# microsd.net
KiCad netlist of a schematic drawn in Altium Designer
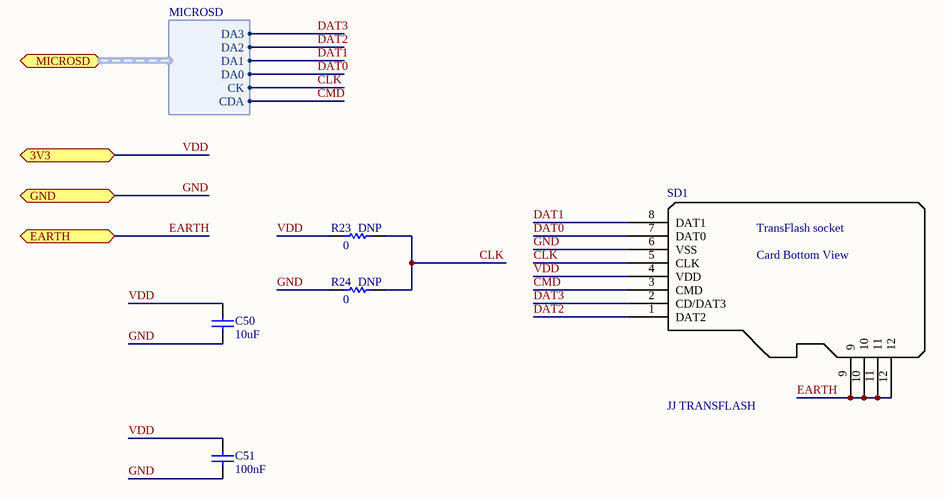
[diagram p0: microsd.SchDoc]

(export (version "E")
  (design (tool "Eeschema 10.0.6"))
  (components
    (comp (ref "C50")
      (value "10uF")
      (footprint "0805")
      (fields (field (name "TOLERANCE") "5%") (field (name "VOLTAGE") "25V") (field (name "Comment") "CAP"))
      (libsource (lib "gasctrl") (part "CAP"))
    )
    (comp (ref "C51")
      (value "100nF")
      (footprint "0805")
      (fields (field (name "TOLERANCE") "5%") (field (name "VOLTAGE") "25V") (field (name "Comment") "CAP"))
      (libsource (lib "gasctrl") (part "CAP"))
    )
    (comp (ref "R23")
      (value "0")
      (footprint "gasctrl:0805")
      (description "RES 0805 0.0 OHM .33W")
      (fields
        (field (name "MANUFACTURER") "Vishay Dale")
        (field (name "POWER") ".33W")
        (field (name "DO NOT PLACE") "DNP")
      )
      (libsource (lib "gasctrl") (part "RES 0805 0.0 Ohm .33W"))
    )
    (comp (ref "R24")
      (value "0")
      (footprint "gasctrl:0805")
      (description "RES 0805 0.0 OHM .33W")
      (fields
        (field (name "MANUFACTURER") "Vishay Dale")
        (field (name "POWER") ".33W")
        (field (name "DO NOT PLACE") "DNP")
      )
      (libsource (lib "gasctrl") (part "RES 0805 0.0 Ohm .33W"))
    )
    (comp (ref "SD1")
      (value "JJ TRANSFLASH")
      (footprint "microSD Socket")
      (description "Transflash Socket")
      (libsource (lib "Schematics") (part "JJ TRANSFLASH"))
    )
  )
  (nets
    (net (code "2") (name "/CLK") (class "Default")
      (node (ref "R23") (pin "2") (pinfunction "2_2") (pintype "passive"))
      (node (ref "R24") (pin "2") (pinfunction "2_2") (pintype "passive"))
      (node (ref "SD1") (pin "5") (pinfunction "CLK_5") (pintype "passive"))
    )
    (net (code "3") (name "/CMD") (class "Default")
      (node (ref "SD1") (pin "3") (pinfunction "CMD_3") (pintype "passive"))
    )
    (net (code "4") (name "/DAT0") (class "Default")
      (node (ref "SD1") (pin "7") (pinfunction "DAT0_7") (pintype "passive"))
    )
    (net (code "5") (name "/DAT1") (class "Default")
      (node (ref "SD1") (pin "8") (pinfunction "DAT1_8") (pintype "passive"))
    )
    (net (code "6") (name "/DAT2") (class "Default")
      (node (ref "SD1") (pin "1") (pinfunction "DAT2_1") (pintype "passive"))
    )
    (net (code "7") (name "/DAT3") (class "Default")
      (node (ref "SD1") (pin "2") (pinfunction "CD/DAT3_2") (pintype "passive"))
    )
    (net (code "8") (name "/EARTH") (class "Default")
      (node (ref "SD1") (pin "10") (pinfunction "10_10") (pintype "passive"))
      (node (ref "SD1") (pin "11") (pinfunction "11_11") (pintype "passive"))
      (node (ref "SD1") (pin "12") (pinfunction "12_12") (pintype "passive"))
      (node (ref "SD1") (pin "9") (pinfunction "9_9") (pintype "passive"))
    )
    (net (code "9") (name "/GND") (class "Default")
      (node (ref "C50") (pin "1") (pinfunction "1_1") (pintype "passive"))
      (node (ref "C51") (pin "1") (pinfunction "1_1") (pintype "passive"))
      (node (ref "R24") (pin "1") (pinfunction "1_1") (pintype "passive"))
      (node (ref "SD1") (pin "6") (pinfunction "VSS_6") (pintype "passive"))
    )
    (net (code "10") (name "/VDD") (class "Default")
      (node (ref "C50") (pin "2") (pinfunction "2_2") (pintype "passive"))
      (node (ref "C51") (pin "2") (pinfunction "2_2") (pintype "passive"))
      (node (ref "R23") (pin "1") (pinfunction "1_1") (pintype "passive"))
      (node (ref "SD1") (pin "4") (pinfunction "VDD_4") (pintype "passive"))
    )
  )
)
